# MAIN_SHEET.net
KiCad netlist of a schematic drawn in Altium Designer
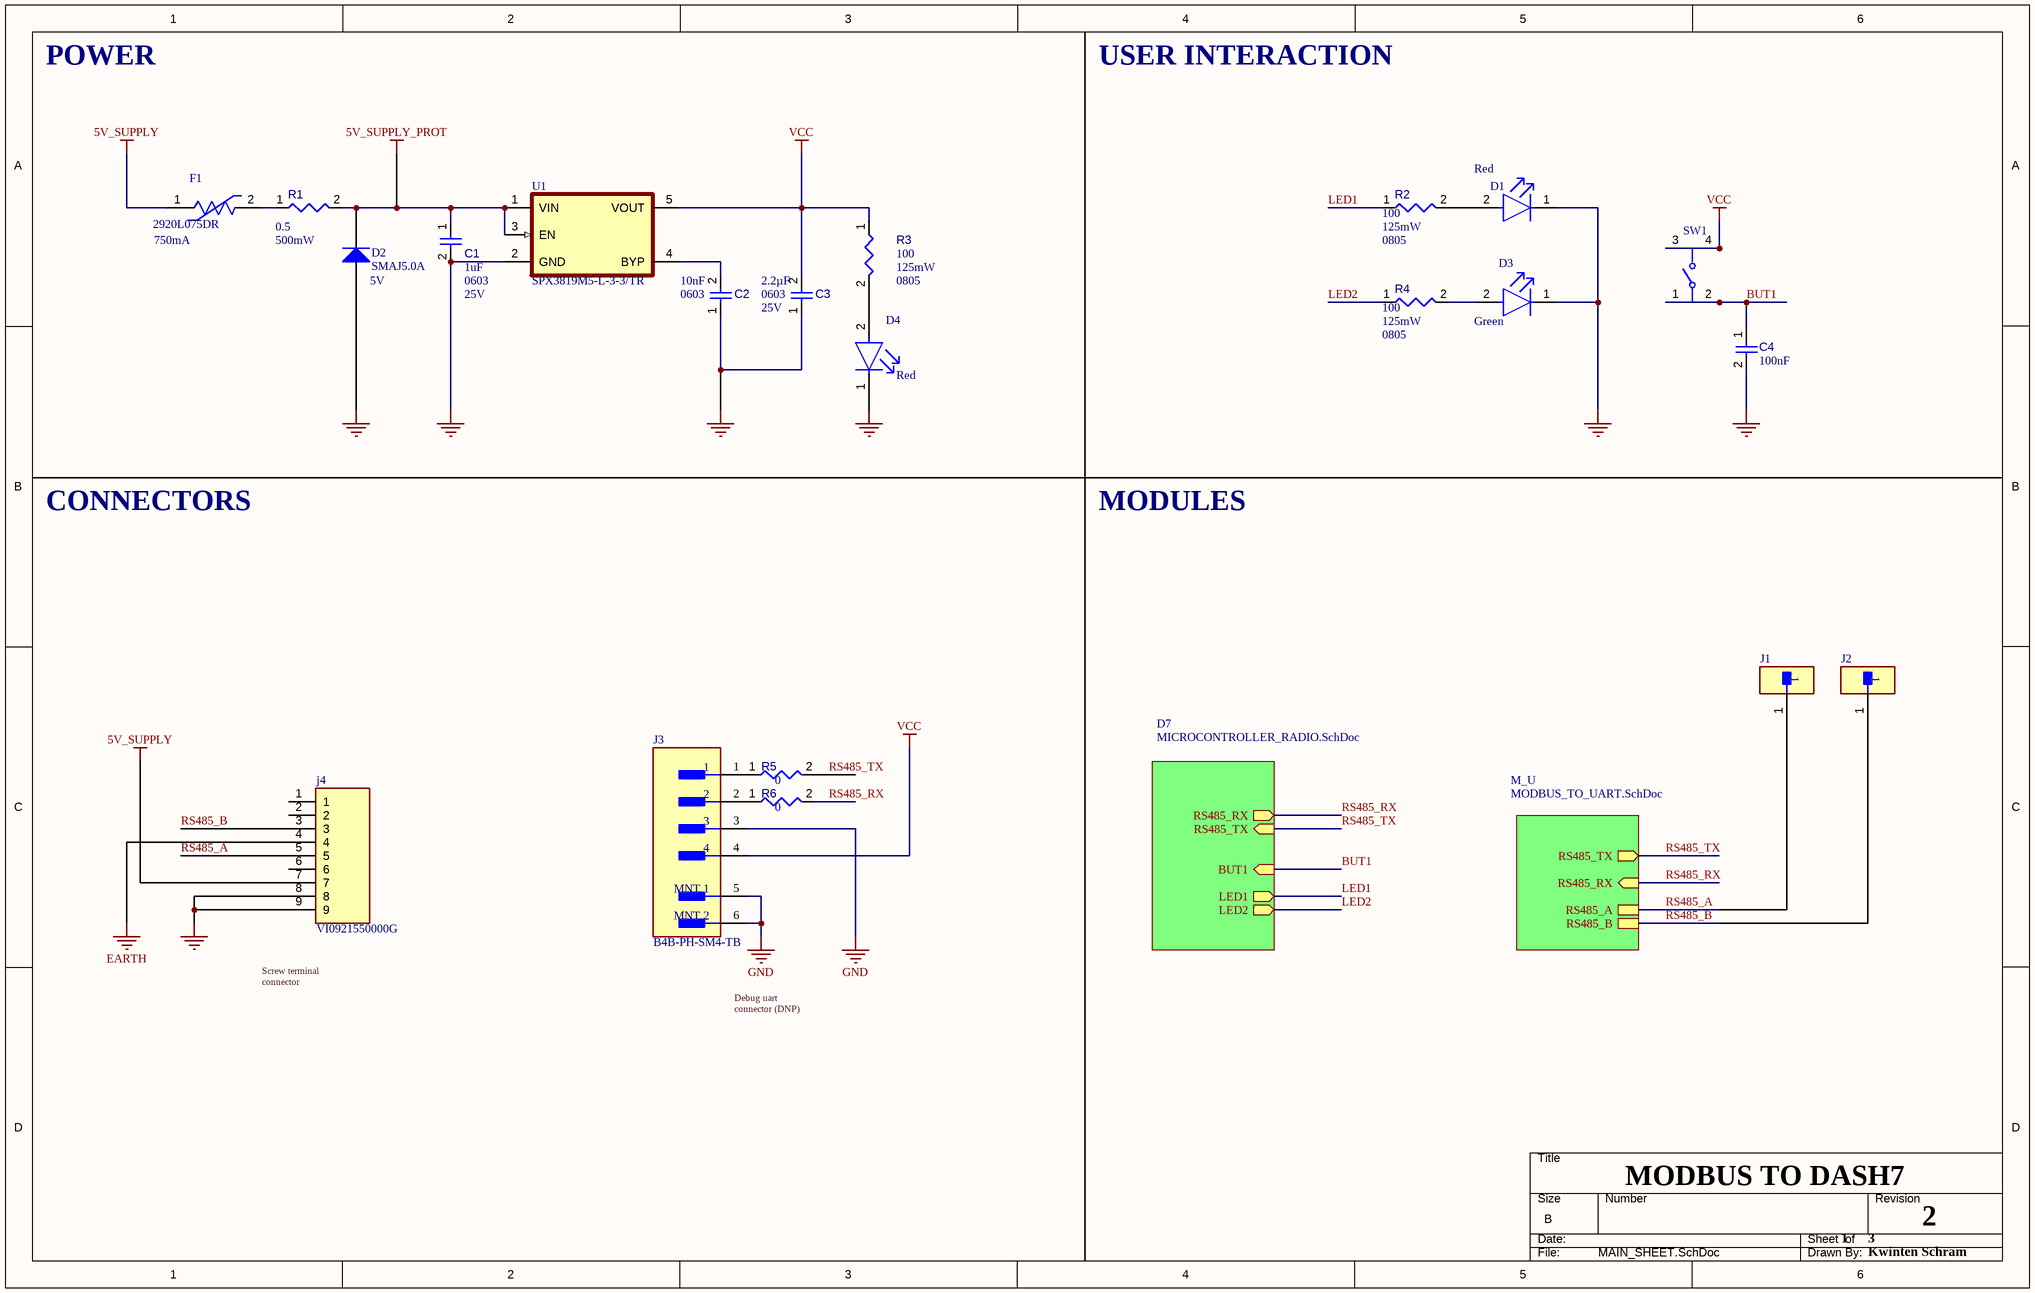
[diagram p0: MAIN_SHEET.SchDoc]

(export (version "E")
  (design (tool "Eeschema 10.0.6"))
  (components
    (comp (ref "C1")
      (value "CC0603KPX7R8BB105")
      (footprint "FP-CC0603-DA-MFG")
      (fields
        (field (name "CAPACITANCE") "1uF")
        (field (name "TOLERANCE") "10%")
        (field (name "VOLTAGE RATING") "25V")
        (field (name "CASE/PACKAGE") "0603")
      )
      (libsource (lib "Altium Concord Pro on A365") (part "CAP-NP-2"))
    )
    (comp (ref "C2")
      (value "10nF")
      (footprint "FP-C0603C-CF-IPC_B")
      (fields
        (field (name "CASE/PACKAGE") "0603")
        (field (name "TOLERANCE") "10%")
        (field (name "Comment") "C0603C103K2RACTU")
      )
      (libsource (lib "Altium Concord Pro on A365") (part "CAP-NP-2"))
    )
    (comp (ref "C3")
      (value "2.2µF")
      (footprint "FP-GRM188-0_2-IPC_C")
      (fields
        (field (name "CASE/PACKAGE") "0603")
        (field (name "TOLERANCE") "10%")
        (field (name "RATED DC VOLTAGE (URDC)") "25V")
        (field (name "Comment") "GRM188Z71E225KE43D")
      )
      (libsource (lib "Altium Concord Pro on A365") (part "CAP-NP-2"))
    )
    (comp (ref "C4")
      (value "100nF")
      (footprint "FP-0603-L_1_6_0_15-W_0_81-MFG")
      (fields (field (name "TOLERANCE") "10%") (field (name "Comment") "06033C104KAT2A"))
      (libsource (lib "Altium Concord Pro on A365") (part "CAP-NP-2"))
    )
    (comp (ref "D1")
      (value "APT1608SURCK")
      (footprint "FP-APT1608EC-MFG")
      (description "Single Color LED, Hyper Red, Water Clear, 1.2mm")
      (fields (field (name "COLOR") "Red"))
      (libsource (lib "Altium Concord Pro on A365") (part "8706943c75ba83719d021d2fdc84c58"))
    )
    (comp (ref "D2")
      (value "SMAJ5.0A")
      (footprint "BOUR-SMA-2_V")
      (description "Trans Voltage Suppressor Diode, 400W, 5V V(RWM), Unidirectional, 1 Element, Silicon, DO-214AC")
      (fields (field (name "FORWARD VOLTAGE") "5V"))
      (libsource (lib "Altium Concord Pro on A365") (part "D-AK-2"))
    )
    (comp (ref "D3")
      (value "APG1608CGKC/T")
      (footprint "FP-APG1608CGKC-T-MFG")
      (description "Single Color LED, Green, Water Clear, 1.2mm")
      (fields (field (name "COLOR") "Green"))
      (libsource (lib "Altium Concord Pro on A365") (part "8706943c75ba83719d021d2fdc84c58"))
    )
    (comp (ref "D4")
      (value "APT1608SURCK")
      (footprint "FP-APT1608EC-MFG")
      (description "Single Color LED, Hyper Red, Water Clear, 1.2mm")
      (fields (field (name "COLOR") "Red"))
      (libsource (lib "Altium Concord Pro on A365") (part "8706943c75ba83719d021d2fdc84c58"))
    )
    (comp (ref "F1")
      (value "2920L075DR")
      (footprint "FP-2920L050DR-MFG")
      (description "PTC Thermistor, 30V, 0.35ohm, Surface Mount")
      (fields (field (name "CURRENT RATING") "750mA"))
      (libsource (lib "Altium Concord Pro on A365") (part "1c6d77a0208143737455a0c7eb396be"))
    )
    (comp (ref "J1")
      (value "PBC01SAAN")
      (footprint "FP-PBC01SAAN-MFG")
      (description "Board Connector, 1 Contact(s), 1 Row(s), Male, Straight, 0.1 inch Pitch, Solder Terminal")
      (libsource (lib "Altium Concord Pro on A365") (part "dd45045ce8184df9e99e12baf3f412c"))
    )
    (comp (ref "J2")
      (value "PBC01SAAN")
      (footprint "FP-PBC01SAAN-MFG")
      (description "Board Connector, 1 Contact(s), 1 Row(s), Male, Straight, 0.1 inch Pitch, Solder Terminal")
      (libsource (lib "Altium Concord Pro on A365") (part "dd45045ce8184df9e99e12baf3f412c"))
    )
    (comp (ref "J3")
      (value "B4B-PH-SM4-TB")
      (footprint "FP-B4B-PH-SM4-TB-MFG")
      (description "Header B4B-PH-SM4-TB, 2.00mm, 4-contacts, top entry, SMT /1000/reel")
      (libsource (lib "Altium Concord Pro on A365") (part "f4320a1371cd6270e33bce1916c33c0"))
    )
    (comp (ref "j4")
      (value "VI0921550000G")
      (footprint "VI0921550000G-Footprint-1")
      (description "Barrier Strip Terminal Block")
      (libsource (lib "Altium Concord Pro on A365") (part "VI0921550000G-Symbol-1"))
    )
    (comp (ref "R1")
      (value "0.5")
      (footprint "RESC3126X65X50NL10T20")
      (fields
        (field (name "POWER") "500mW")
        (field (name "TOLERANCE") "1%")
        (field (name "Comment") "RL1210FR-070R5L")
      )
      (libsource (lib "Altium Concord Pro on A365") (part "RES-2"))
    )
    (comp (ref "R2")
      (value "100")
      (footprint "FP-AC0805-IPC_A")
      (fields
        (field (name "TOLERANCE") "1%")
        (field (name "CASE/PACKAGE") "0805")
        (field (name "POWER") "125mW")
        (field (name "Comment") "AC0805FR-07100RL")
      )
      (libsource (lib "Altium Concord Pro on A365") (part "RES-2"))
    )
    (comp (ref "R3")
      (value "100")
      (footprint "FP-AC0805-IPC_A")
      (fields
        (field (name "TOLERANCE") "1%")
        (field (name "CASE/PACKAGE") "0805")
        (field (name "POWER") "125mW")
        (field (name "Comment") "AC0805FR-07100RL")
      )
      (libsource (lib "Altium Concord Pro on A365") (part "RES-2"))
    )
    (comp (ref "R4")
      (value "100")
      (footprint "FP-AC0805-IPC_A")
      (fields
        (field (name "TOLERANCE") "1%")
        (field (name "CASE/PACKAGE") "0805")
        (field (name "POWER") "125mW")
        (field (name "Comment") "AC0805FR-07100RL")
      )
      (libsource (lib "Altium Concord Pro on A365") (part "RES-2"))
    )
    (comp (ref "R5")
      (value "0")
      (footprint "FP-CRCW0402-e3-IPC_A")
      (description "Metal Glaze/thick Film, 0.063W, 0ohm, Surface Mount, 0402")
      (fields (field (name "POWER") "63mW") (field (name "Comment") "CRCW04020000Z0ED"))
      (libsource (lib "Altium Concord Pro on A365") (part "RES-2"))
    )
    (comp (ref "R6")
      (value "0")
      (footprint "FP-CRCW0402-e3-IPC_A")
      (description "Metal Glaze/thick Film, 0.063W, 0ohm, Surface Mount, 0402")
      (fields (field (name "POWER") "63mW") (field (name "Comment") "CRCW04020000Z0ED"))
      (libsource (lib "Altium Concord Pro on A365") (part "RES-2"))
    )
    (comp (ref "SW1")
      (value "PTS526SK15SMTR2LFS")
      (footprint "FP-PTS526SK15SMTR2LFS-MFG")
      (description "TACT 5.2 X 5.2, 1.5 MM H, 260GF,")
      (fields
        (field (name "MANUFACTURER") "C&K")
        (field (name "OCTOPART") "https://octopart.com/pts526+sk15+smtr2+lfs-c%26k+components-100617999")
      )
      (libsource (lib "Altium Content Vault") (part "b8895f3f4cefb76e1819d2863dba89b"))
    )
    (comp (ref "U1")
      (value "SPX3819M5-L-3-3/TR")
      (footprint "SOT95P280X145-5N")
      (description "Fixed Positive LDO Regulator, 3.3V, 0.7V Dropout, PDSO5")
      (fields (field (name "MF") "MaxLinear, Inc.") (field (name "DIGI-KEY_PART_NUMBER") "1016-1873-1-ND"))
      (libsource (lib "Altium Concord Pro on A365") (part "SPX3819M5-L-3-3"))
    )
  )
  (nets
    (net (code "1") (name "/BUT1") (class "Default")
      (node (ref "C4") (pin "1") (pinfunction "1_1") (pintype "passive"))
      (node (ref "SW1") (pin "1") (pinfunction "1_1") (pintype "passive"))
      (node (ref "SW1") (pin "2") (pinfunction "2_2") (pintype "passive"))
    )
    (net (code "2") (name "/LED1") (class "Default")
      (node (ref "R2") (pin "1") (pinfunction "1_1") (pintype "passive"))
    )
    (net (code "3") (name "/LED2") (class "Default")
      (node (ref "R4") (pin "1") (pinfunction "1_1") (pintype "passive"))
    )
    (net (code "4") (name "/RS485_A") (class "Default")
      (node (ref "J1") (pin "1") (pinfunction "1_1") (pintype "passive"))
      (node (ref "j4") (pin "5") (pinfunction "5_5") (pintype "passive"))
    )
    (net (code "5") (name "/RS485_B") (class "Default")
      (node (ref "J2") (pin "1") (pinfunction "1_1") (pintype "passive"))
      (node (ref "j4") (pin "3") (pinfunction "3_3") (pintype "passive"))
    )
    (net (code "6") (name "/RS485_RX") (class "Default")
      (node (ref "R6") (pin "2") (pinfunction "2_2") (pintype "passive"))
    )
    (net (code "7") (name "/RS485_TX") (class "Default")
      (node (ref "R5") (pin "2") (pinfunction "2_2") (pintype "passive"))
    )
    (net (code "8") (name "5V_SUPPLY") (class "Default")
      (node (ref "F1") (pin "1") (pinfunction "1_1") (pintype "passive"))
      (node (ref "j4") (pin "7") (pinfunction "7_7") (pintype "passive"))
    )
    (net (code "9") (name "5V_SUPPLY_PROT") (class "Default")
      (node (ref "C1") (pin "1") (pinfunction "1_1") (pintype "passive"))
      (node (ref "D2") (pin "2") (pinfunction "K_2") (pintype "passive"))
      (node (ref "R1") (pin "2") (pinfunction "2_2") (pintype "passive"))
      (node (ref "U1") (pin "1") (pinfunction "VIN_1") (pintype "power_in"))
      (node (ref "U1") (pin "3") (pinfunction "EN_3") (pintype "input"))
    )
    (net (code "10") (name "EARTH") (class "Default")
      (node (ref "j4") (pin "4") (pinfunction "4_4") (pintype "passive"))
    )
    (net (code "11") (name "GND") (class "Default")
      (node (ref "C1") (pin "2") (pinfunction "2_2") (pintype "passive"))
      (node (ref "C2") (pin "1") (pinfunction "1_1") (pintype "passive"))
      (node (ref "C3") (pin "1") (pinfunction "1_1") (pintype "passive"))
      (node (ref "C4") (pin "2") (pinfunction "2_2") (pintype "passive"))
      (node (ref "D1") (pin "1") (pinfunction "C_1") (pintype "passive"))
      (node (ref "D2") (pin "1") (pinfunction "A_1") (pintype "passive"))
      (node (ref "D3") (pin "1") (pinfunction "C_1") (pintype "passive"))
      (node (ref "D4") (pin "1") (pinfunction "C_1") (pintype "passive"))
      (node (ref "J3") (pin "3") (pinfunction "3_3") (pintype "passive"))
      (node (ref "J3") (pin "5") (pinfunction "MNT_1_5") (pintype "passive"))
      (node (ref "J3") (pin "6") (pinfunction "MNT_2_6") (pintype "passive"))
      (node (ref "U1") (pin "2") (pinfunction "GND_2") (pintype "passive"))
      (node (ref "j4") (pin "8") (pinfunction "8_8") (pintype "passive"))
      (node (ref "j4") (pin "9") (pinfunction "9_9") (pintype "passive"))
    )
    (net (code "12") (name "Net-(D1-A)") (class "Default")
      (node (ref "D1") (pin "2") (pinfunction "A_2") (pintype "passive"))
      (node (ref "R2") (pin "2") (pinfunction "2_2") (pintype "passive"))
    )
    (net (code "13") (name "Net-(D3-A)") (class "Default")
      (node (ref "D3") (pin "2") (pinfunction "A_2") (pintype "passive"))
      (node (ref "R4") (pin "2") (pinfunction "2_2") (pintype "passive"))
    )
    (net (code "14") (name "Net-(D4-A)") (class "Default")
      (node (ref "D4") (pin "2") (pinfunction "A_2") (pintype "passive"))
      (node (ref "R3") (pin "2") (pinfunction "2_2") (pintype "passive"))
    )
    (net (code "15") (name "Net-(F1-Pad2)") (class "Default")
      (node (ref "F1") (pin "2") (pinfunction "2_2") (pintype "passive"))
      (node (ref "R1") (pin "1") (pinfunction "1_1") (pintype "passive"))
    )
    (net (code "16") (name "Net-(J3-Pad1)") (class "Default")
      (node (ref "J3") (pin "1") (pinfunction "1_1") (pintype "passive"))
      (node (ref "R5") (pin "1") (pinfunction "1_1") (pintype "passive"))
    )
    (net (code "17") (name "Net-(J3-Pad2)") (class "Default")
      (node (ref "J3") (pin "2") (pinfunction "2_2") (pintype "passive"))
      (node (ref "R6") (pin "1") (pinfunction "1_1") (pintype "passive"))
    )
    (net (code "18") (name "Net-(U1-BYP)") (class "Default")
      (node (ref "C2") (pin "2") (pinfunction "2_2") (pintype "passive"))
      (node (ref "U1") (pin "4") (pinfunction "BYP_4") (pintype "passive"))
    )
    (net (code "19") (name "VCC") (class "Default")
      (node (ref "C3") (pin "2") (pinfunction "2_2") (pintype "passive"))
      (node (ref "J3") (pin "4") (pinfunction "4_4") (pintype "passive"))
      (node (ref "R3") (pin "1") (pinfunction "1_1") (pintype "passive"))
      (node (ref "SW1") (pin "3") (pinfunction "3_3") (pintype "passive"))
      (node (ref "SW1") (pin "4") (pinfunction "4_4") (pintype "passive"))
      (node (ref "U1") (pin "5") (pinfunction "VOUT_5") (pintype "power_in"))
    )
    (net (code "20") (name "unconnected-(j4-Pad1)") (class "Default")
      (node (ref "j4") (pin "1") (pinfunction "1_1") (pintype "passive"))
    )
    (net (code "21") (name "unconnected-(j4-Pad2)") (class "Default")
      (node (ref "j4") (pin "2") (pinfunction "2_2") (pintype "passive"))
    )
    (net (code "22") (name "unconnected-(j4-Pad6)") (class "Default")
      (node (ref "j4") (pin "6") (pinfunction "6_6") (pintype "passive"))
    )
  )
)
